# STPMS2_PT100.net
KiCad netlist of a schematic drawn in Altium Designer
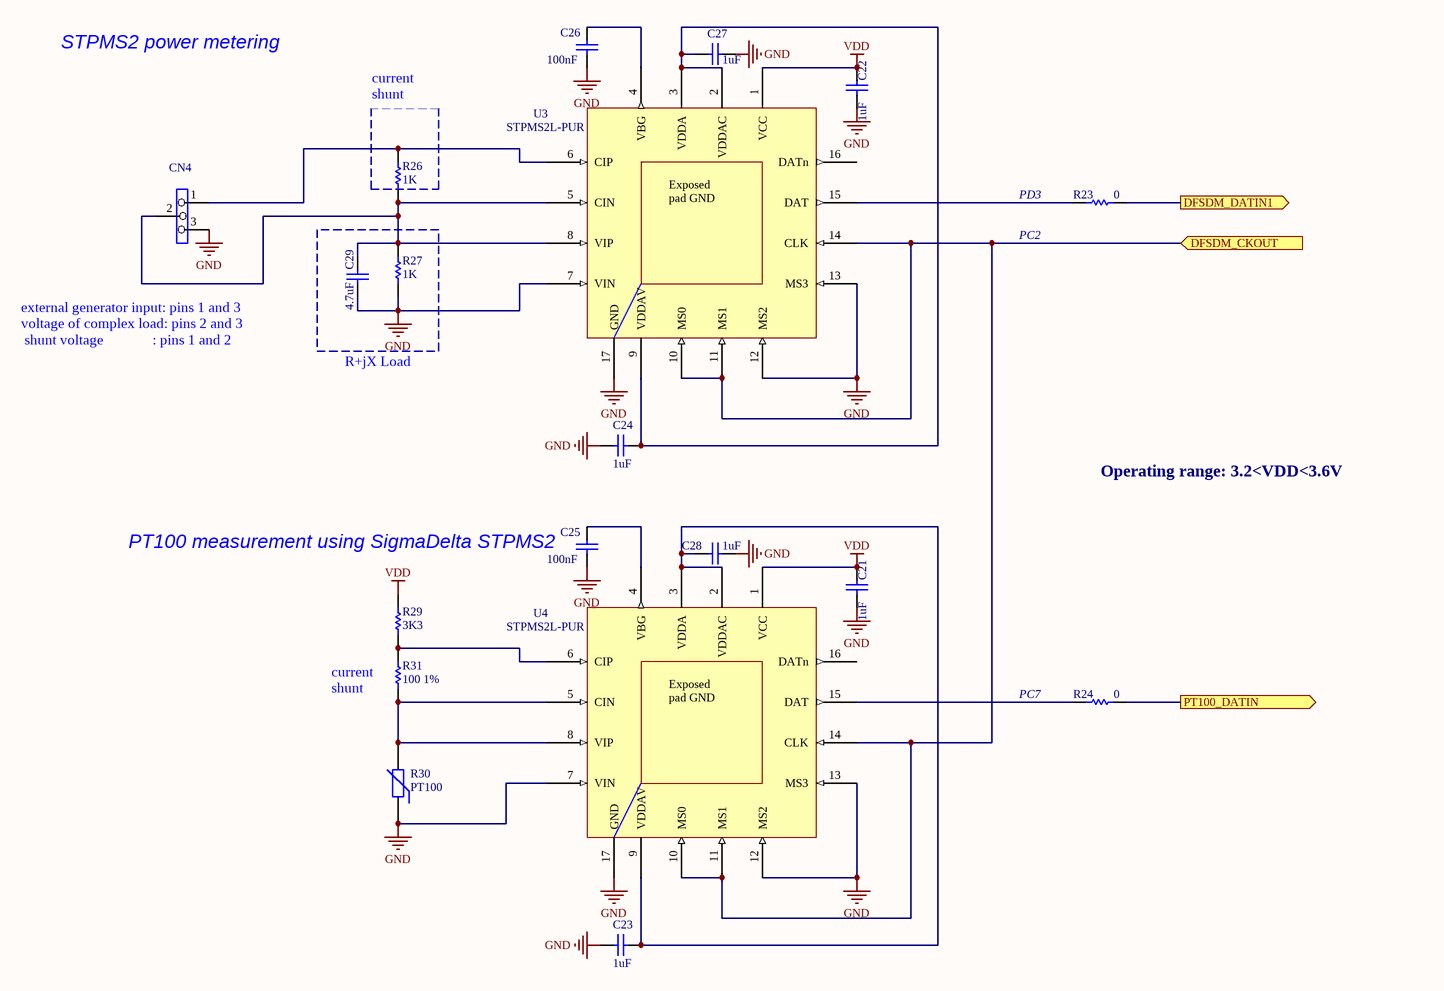
[diagram p0: STPMS2&PT100.SchDoc]

(export (version "E")
  (design (tool "Eeschema 10.0.6"))
  (components
    (comp (ref "C21")
      (value "1uF")
      (footprint "0603C")
      (description "Capacitor")
      (fields (field (name "PUBLISHER") "Altium Limited"))
      (libsource (lib "Miscellaneous Devices") (part "CAP"))
    )
    (comp (ref "C22")
      (value "1uF")
      (footprint "0603C")
      (description "Capacitor")
      (fields (field (name "PUBLISHER") "Altium Limited"))
      (libsource (lib "Miscellaneous Devices") (part "CAP"))
    )
    (comp (ref "C23")
      (value "1uF")
      (footprint "0603C")
      (description "Capacitor")
      (fields (field (name "PUBLISHER") "Altium Limited"))
      (libsource (lib "Miscellaneous Devices") (part "CAP"))
    )
    (comp (ref "C24")
      (value "1uF")
      (footprint "0603C")
      (description "Capacitor")
      (fields (field (name "PUBLISHER") "Altium Limited"))
      (libsource (lib "Miscellaneous Devices") (part "CAP"))
    )
    (comp (ref "C25")
      (value "100nF")
      (footprint "0402C")
      (description "Capacitor")
      (fields (field (name "PUBLISHER") "Altium Limited"))
      (libsource (lib "Miscellaneous Devices") (part "Cap"))
    )
    (comp (ref "C26")
      (value "100nF")
      (footprint "0402C")
      (description "Capacitor")
      (fields (field (name "PUBLISHER") "Altium Limited"))
      (libsource (lib "Miscellaneous Devices") (part "Cap"))
    )
    (comp (ref "C27")
      (value "1uF")
      (footprint "0603C")
      (description "Capacitor")
      (fields (field (name "PUBLISHER") "Altium Limited"))
      (libsource (lib "Miscellaneous Devices") (part "CAP"))
    )
    (comp (ref "C28")
      (value "1uF")
      (footprint "0603C")
      (description "Capacitor")
      (fields (field (name "PUBLISHER") "Altium Limited"))
      (libsource (lib "Miscellaneous Devices") (part "CAP"))
    )
    (comp (ref "C29")
      (value "4.7uF")
      (footprint "0603C")
      (description "Capacitor")
      (fields (field (name "PUBLISHER") "Altium Limited"))
      (libsource (lib "Miscellaneous Devices") (part "CAP"))
    )
    (comp (ref "CN4")
      (value "Header 3X1")
      (footprint "SIP3")
      (libsource (lib "STR910_SCHLIB") (part "Jumper3"))
    )
    (comp (ref "R23")
      (value "0")
      (footprint "0603R")
      (description "Resistor")
      (fields (field (name "PUBLISHER") "Altium Limited"))
      (libsource (lib "Miscellaneous Devices") (part "res1"))
    )
    (comp (ref "R24")
      (value "0")
      (footprint "0603R")
      (description "Resistor")
      (fields (field (name "PUBLISHER") "Altium Limited"))
      (libsource (lib "Miscellaneous Devices") (part "res1"))
    )
    (comp (ref "R26")
      (value "1K")
      (footprint "0402R")
      (description "Resistor")
      (fields (field (name "PUBLISHER") "Altium Limited"))
      (libsource (lib "Miscellaneous Devices") (part "Res1"))
    )
    (comp (ref "R27")
      (value "1K")
      (footprint "0402R")
      (description "Resistor")
      (fields (field (name "PUBLISHER") "Altium Limited"))
      (libsource (lib "Miscellaneous Devices") (part "Res1"))
    )
    (comp (ref "R29")
      (value "3K3")
      (footprint "0402R")
      (description "Resistor")
      (fields (field (name "PUBLISHER") "Altium Limited"))
      (libsource (lib "Miscellaneous Devices") (part "Res1"))
    )
    (comp (ref "R30")
      (value "PT100")
      (footprint "HDR_1X2_1R27")
      (description "Varistor (Voltage-Sensitive Resistor)")
      (fields (field (name "PUBLISHER") "Altium Limited"))
      (libsource (lib "MB988") (part "PT100"))
    )
    (comp (ref "R31")
      (value "100 1%")
      (footprint "0603R")
      (description "Resistor")
      (fields (field (name "PUBLISHER") "Altium Limited"))
      (libsource (lib "Miscellaneous Devices") (part "Res1"))
    )
    (comp (ref "U3")
      (value "STPMS2L-PUR")
      (footprint "QFN16_0R65_4X4")
      (description "STM sigmaDelta modulator")
      (libsource (lib "orcaeval_2") (part "STPMS2"))
    )
    (comp (ref "U4")
      (value "STPMS2L-PUR")
      (footprint "QFN16_0R65_4X4")
      (description "STM sigmaDelta modulator")
      (libsource (lib "orcaeval_2") (part "STPMS2"))
    )
  )
  (nets
    (net (code "1") (name "/DFSDM_CKOUT") (class "Default")
      (node (ref "U3") (pin "10") (pinfunction "MS0_10") (pintype "input"))
      (node (ref "U3") (pin "11") (pinfunction "MS1_11") (pintype "input"))
      (node (ref "U3") (pin "14") (pinfunction "CLK_14") (pintype "input"))
      (node (ref "U4") (pin "10") (pinfunction "MS0_10") (pintype "input"))
      (node (ref "U4") (pin "11") (pinfunction "MS1_11") (pintype "input"))
      (node (ref "U4") (pin "14") (pinfunction "CLK_14") (pintype "input"))
    )
    (net (code "2") (name "/DFSDM_DATIN1") (class "Default")
      (node (ref "R23") (pin "1") (pinfunction "1_1") (pintype "passive"))
    )
    (net (code "3") (name "/PT100_DATIN") (class "Default")
      (node (ref "R24") (pin "1") (pinfunction "1_1") (pintype "passive"))
    )
    (net (code "4") (name "GND") (class "Default")
      (node (ref "C21") (pin "2") (pinfunction "2_2") (pintype "passive"))
      (node (ref "C22") (pin "2") (pinfunction "2_2") (pintype "passive"))
      (node (ref "C23") (pin "1") (pinfunction "1_1") (pintype "passive"))
      (node (ref "C24") (pin "1") (pinfunction "1_1") (pintype "passive"))
      (node (ref "C25") (pin "1") (pinfunction "1_1") (pintype "passive"))
      (node (ref "C26") (pin "1") (pinfunction "1_1") (pintype "passive"))
      (node (ref "C27") (pin "2") (pinfunction "2_2") (pintype "passive"))
      (node (ref "C28") (pin "2") (pinfunction "2_2") (pintype "passive"))
      (node (ref "C29") (pin "2") (pinfunction "2_2") (pintype "passive"))
      (node (ref "CN4") (pin "3") (pintype "passive"))
      (node (ref "R27") (pin "2") (pinfunction "2_2") (pintype "passive"))
      (node (ref "R30") (pin "1") (pinfunction "1_1") (pintype "passive"))
      (node (ref "U3") (pin "12") (pinfunction "MS2_12") (pintype "input"))
      (node (ref "U3") (pin "13") (pinfunction "MS3_13") (pintype "input"))
      (node (ref "U3") (pin "17") (pinfunction "GND_17") (pintype "power_in"))
      (node (ref "U3") (pin "7") (pinfunction "VIN_7") (pintype "input"))
      (node (ref "U4") (pin "12") (pinfunction "MS2_12") (pintype "input"))
      (node (ref "U4") (pin "13") (pinfunction "MS3_13") (pintype "input"))
      (node (ref "U4") (pin "17") (pinfunction "GND_17") (pintype "power_in"))
      (node (ref "U4") (pin "7") (pinfunction "VIN_7") (pintype "input"))
    )
    (net (code "5") (name "Net-(U3-CIN)") (class "Default")
      (node (ref "C29") (pin "1") (pinfunction "1_1") (pintype "passive"))
      (node (ref "CN4") (pin "2") (pintype "passive"))
      (node (ref "R26") (pin "2") (pinfunction "2_2") (pintype "passive"))
      (node (ref "R27") (pin "1") (pinfunction "1_1") (pintype "passive"))
      (node (ref "U3") (pin "5") (pinfunction "CIN_5") (pintype "input"))
      (node (ref "U3") (pin "8") (pinfunction "VIP_8") (pintype "input"))
    )
    (net (code "6") (name "Net-(U3-CIP)") (class "Default")
      (node (ref "CN4") (pin "1") (pintype "passive"))
      (node (ref "R26") (pin "1") (pinfunction "1_1") (pintype "passive"))
      (node (ref "U3") (pin "6") (pinfunction "CIP_6") (pintype "input"))
    )
    (net (code "7") (name "Net-(U3-DAT)") (class "Default")
      (node (ref "R23") (pin "2") (pinfunction "2_2") (pintype "passive"))
      (node (ref "U3") (pin "15") (pinfunction "DAT_15") (pintype "output"))
    )
    (net (code "8") (name "Net-(U3-VBG)") (class "Default")
      (node (ref "C26") (pin "2") (pinfunction "2_2") (pintype "passive"))
      (node (ref "U3") (pin "4") (pinfunction "VBG_4") (pintype "output"))
    )
    (net (code "9") (name "Net-(U3-VDDA)") (class "Default")
      (node (ref "C24") (pin "2") (pinfunction "2_2") (pintype "passive"))
      (node (ref "C27") (pin "1") (pinfunction "1_1") (pintype "passive"))
      (node (ref "U3") (pin "2") (pinfunction "VDDAC_2") (pintype "power_in"))
      (node (ref "U3") (pin "3") (pinfunction "VDDA_3") (pintype "power_in"))
      (node (ref "U3") (pin "9") (pinfunction "VDDAV_9") (pintype "power_in"))
    )
    (net (code "10") (name "Net-(U4-CIN)") (class "Default")
      (node (ref "R30") (pin "2") (pinfunction "2_2") (pintype "passive"))
      (node (ref "R31") (pin "2") (pinfunction "2_2") (pintype "passive"))
      (node (ref "U4") (pin "5") (pinfunction "CIN_5") (pintype "input"))
      (node (ref "U4") (pin "8") (pinfunction "VIP_8") (pintype "input"))
    )
    (net (code "11") (name "Net-(U4-CIP)") (class "Default")
      (node (ref "R29") (pin "2") (pinfunction "2_2") (pintype "passive"))
      (node (ref "R31") (pin "1") (pinfunction "1_1") (pintype "passive"))
      (node (ref "U4") (pin "6") (pinfunction "CIP_6") (pintype "input"))
    )
    (net (code "12") (name "Net-(U4-DAT)") (class "Default")
      (node (ref "R24") (pin "2") (pinfunction "2_2") (pintype "passive"))
      (node (ref "U4") (pin "15") (pinfunction "DAT_15") (pintype "output"))
    )
    (net (code "13") (name "Net-(U4-VBG)") (class "Default")
      (node (ref "C25") (pin "2") (pinfunction "2_2") (pintype "passive"))
      (node (ref "U4") (pin "4") (pinfunction "VBG_4") (pintype "output"))
    )
    (net (code "14") (name "Net-(U4-VDDA)") (class "Default")
      (node (ref "C23") (pin "2") (pinfunction "2_2") (pintype "passive"))
      (node (ref "C28") (pin "1") (pinfunction "1_1") (pintype "passive"))
      (node (ref "U4") (pin "2") (pinfunction "VDDAC_2") (pintype "power_in"))
      (node (ref "U4") (pin "3") (pinfunction "VDDA_3") (pintype "power_in"))
      (node (ref "U4") (pin "9") (pinfunction "VDDAV_9") (pintype "power_in"))
    )
    (net (code "15") (name "VDD") (class "Default")
      (node (ref "C21") (pin "1") (pinfunction "1_1") (pintype "passive"))
      (node (ref "C22") (pin "1") (pinfunction "1_1") (pintype "passive"))
      (node (ref "R29") (pin "1") (pinfunction "1_1") (pintype "passive"))
      (node (ref "U3") (pin "1") (pinfunction "VCC_1") (pintype "power_in"))
      (node (ref "U4") (pin "1") (pinfunction "VCC_1") (pintype "power_in"))
    )
    (net (code "16") (name "unconnected-(U3-DATn-Pad16)") (class "Default")
      (node (ref "U3") (pin "16") (pinfunction "DATn_16") (pintype "output"))
    )
    (net (code "17") (name "unconnected-(U4-DATn-Pad16)") (class "Default")
      (node (ref "U4") (pin "16") (pinfunction "DATn_16") (pintype "output"))
    )
  )
)
